# ASD2101.net
KiCad netlist of a schematic drawn in EAGLE
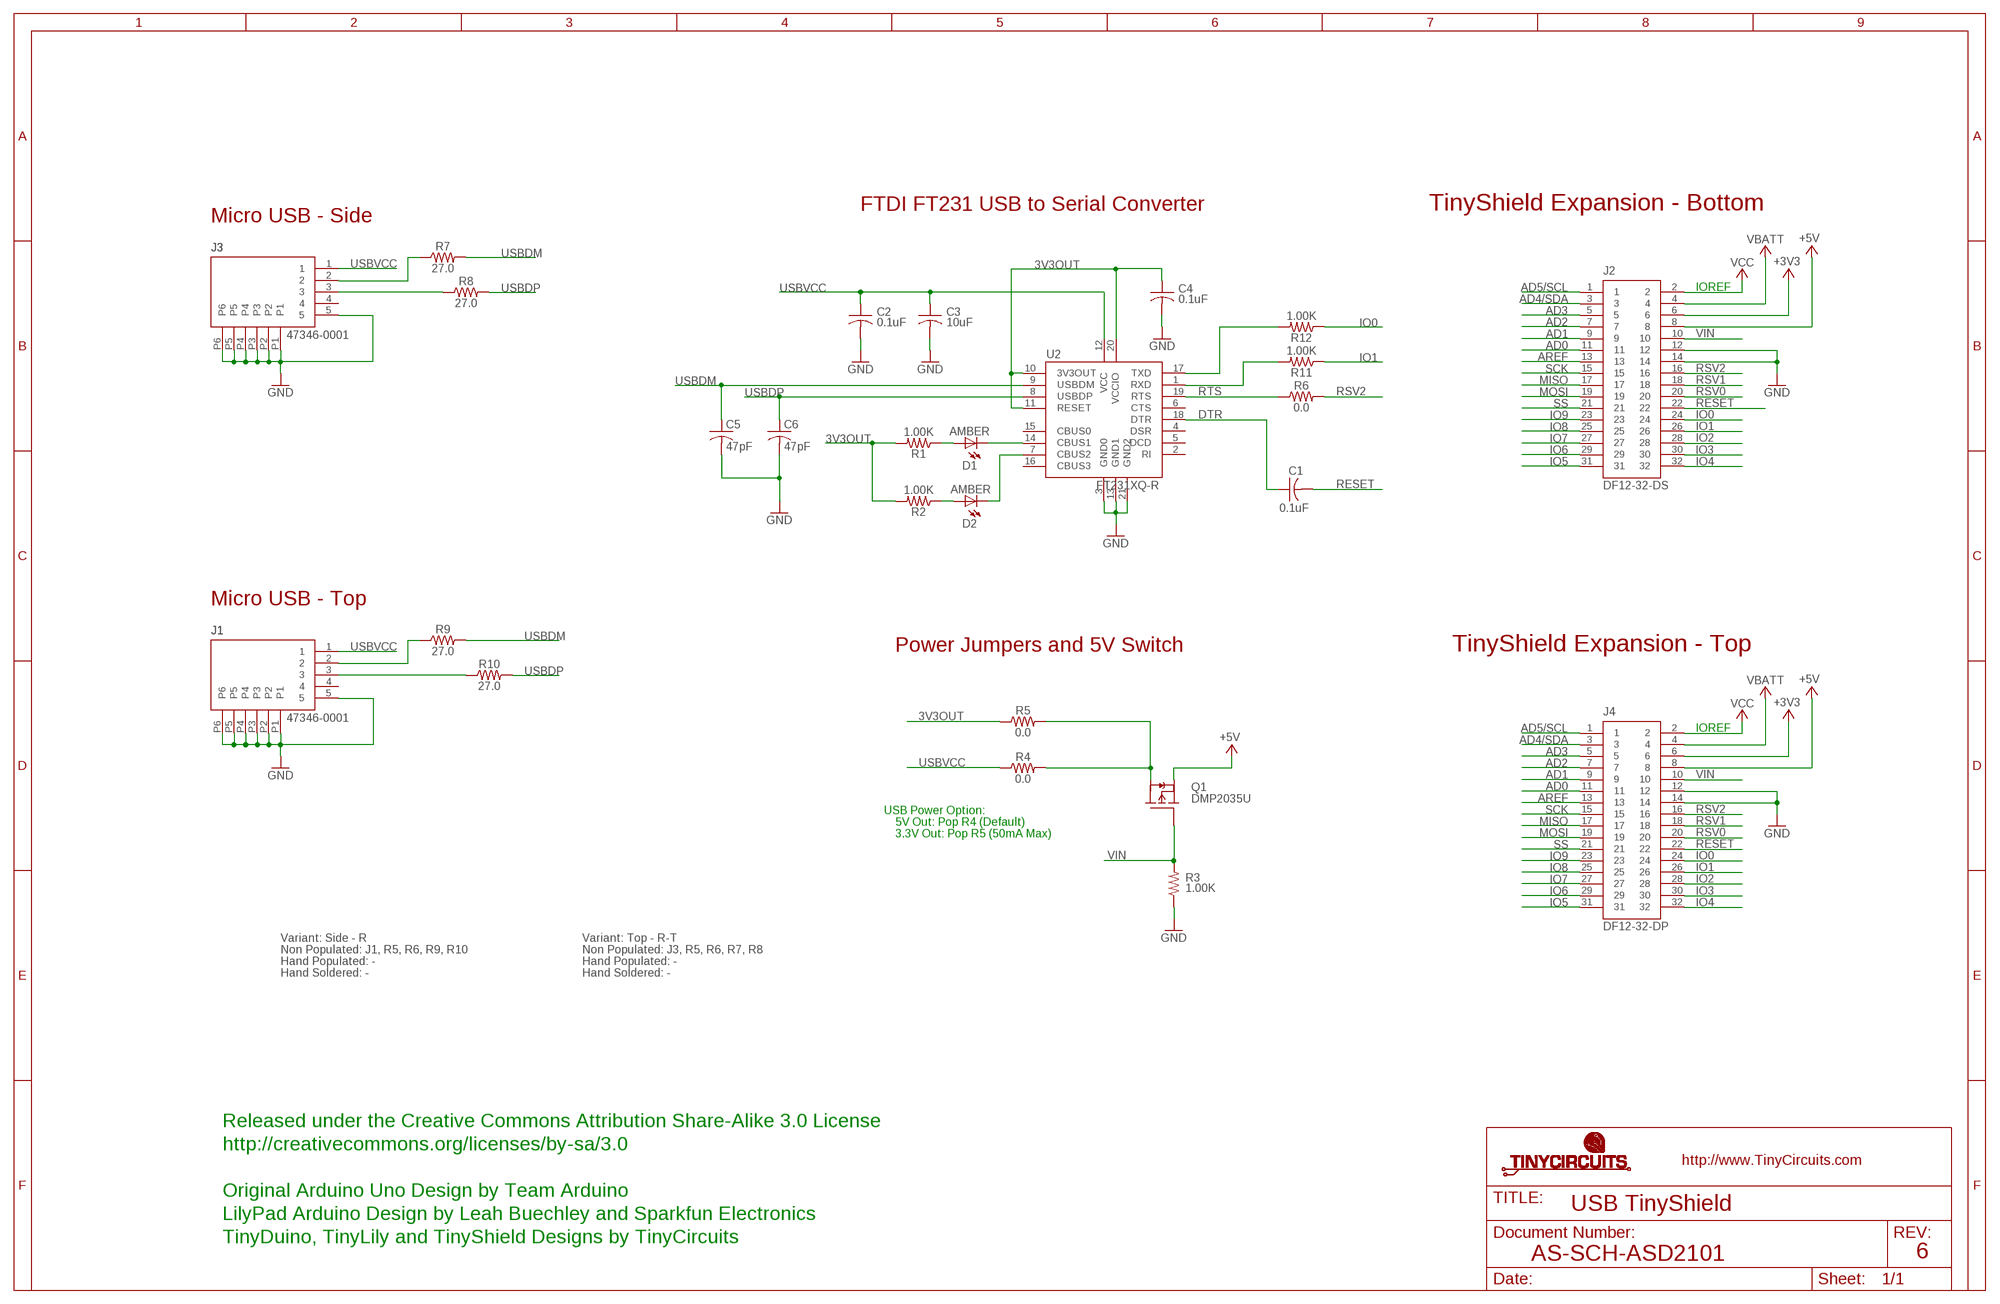
[diagram p0: schematic, sheet 1]

(export (version "E")
  (design (tool "Eeschema 10.0.6"))
  (components
    (comp (ref "C1")
      (value "0.1uF")
      (footprint "eagle-import:C0402")
      (fields (field (name "PARTNO") "AS-ITM-00008") (field (name "PARTNO_1") "AS-ITM-00008"))
      (libsource (lib "eagle-import") (part "AS-ITM-00008"))
    )
    (comp (ref "C2")
      (value "0.1uF")
      (footprint "eagle-import:C0402")
      (fields (field (name "PARTNO") "AS-ITM-00008"))
      (libsource (lib "eagle-import") (part "AS-ITM-00008"))
    )
    (comp (ref "C3")
      (value "10uF")
      (footprint "eagle-import:C0603")
      (fields (field (name "PARTNO") "AS-ITM-00002"))
      (libsource (lib "eagle-import") (part "AS-ITM-00002"))
    )
    (comp (ref "C4")
      (value "0.1uF")
      (footprint "eagle-import:C0402")
      (fields (field (name "PARTNO") "AS-ITM-00008") (field (name "PARTNO_1") "AS-ITM-00008"))
      (libsource (lib "eagle-import") (part "AS-ITM-00008"))
    )
    (comp (ref "C5")
      (value "47pF")
      (footprint "eagle-import:0402")
      (fields (field (name "PARTNO") "AS-ITM-00241") (field (name "PARTNO_1") "AS-ITM-00241"))
      (libsource (lib "eagle-import") (part "AS-ITM-00241"))
    )
    (comp (ref "C6")
      (value "47pF")
      (footprint "eagle-import:0402")
      (fields (field (name "PARTNO") "AS-ITM-00241") (field (name "PARTNO_1") "AS-ITM-00241"))
      (libsource (lib "eagle-import") (part "AS-ITM-00241"))
    )
    (comp (ref "D1")
      (value "AMBER")
      (footprint "eagle-import:LNJ_LED")
      (fields (field (name "PARTNO") "AS-ITM-00026"))
      (libsource (lib "eagle-import") (part "AS-ITM-00026"))
    )
    (comp (ref "D2")
      (value "AMBER")
      (footprint "eagle-import:LNJ_LED")
      (fields (field (name "PARTNO") "AS-ITM-00026"))
      (libsource (lib "eagle-import") (part "AS-ITM-00026"))
    )
    (comp (ref "J1")
      (value "47346-0001")
      (footprint "eagle-import:MICRO_USB")
      (fields (field (name "PARTNO") "AS-ITM-00021") (field (name "PARTNO_1") "AS-ITM-00021"))
      (libsource (lib "eagle-import") (part "AS-ITM-00021"))
    )
    (comp (ref "J2")
      (value "DF12-32-DS")
      (footprint "eagle-import:DF12-32-DS")
      (fields (field (name "PARTNO") "AS-ITM-00012") (field (name "PARTNO_1") "AS-ITM-00012"))
      (libsource (lib "eagle-import") (part "AS-ITM-00012"))
    )
    (comp (ref "J3")
      (value "47346-0001")
      (footprint "eagle-import:MICRO_USB")
      (fields (field (name "PARTNO") "AS-ITM-00021") (field (name "PARTNO_1") "AS-ITM-00021"))
      (libsource (lib "eagle-import") (part "AS-ITM-00021"))
    )
    (comp (ref "J4")
      (value "DF12-32-DP")
      (footprint "eagle-import:DF12-32-DP")
      (fields (field (name "PARTNO") "AS-ITM-00015") (field (name "PARTNO_1") "AS-ITM-00015"))
      (libsource (lib "eagle-import") (part "AS-ITM-00015"))
    )
    (comp (ref "Q1")
      (value "DMP2035U")
      (footprint "eagle-import:SOT23")
      (fields (field (name "PARTNO") "AS-ITM-00024"))
      (libsource (lib "eagle-import") (part "AS-ITM-00024"))
    )
    (comp (ref "R1")
      (value "1.00K")
      (footprint "eagle-import:0402")
      (fields (field (name "PARTNO") "AS-ITM-00003"))
      (libsource (lib "eagle-import") (part "AS-ITM-00003"))
    )
    (comp (ref "R2")
      (value "1.00K")
      (footprint "eagle-import:0402")
      (fields (field (name "PARTNO") "AS-ITM-00003"))
      (libsource (lib "eagle-import") (part "AS-ITM-00003"))
    )
    (comp (ref "R3")
      (value "1.00K")
      (footprint "eagle-import:0402")
      (fields (field (name "PARTNO") "AS-ITM-00003"))
      (libsource (lib "eagle-import") (part "AS-ITM-00003"))
    )
    (comp (ref "R4")
      (value "0.0")
      (footprint "eagle-import:0402")
      (fields (field (name "PARTNO") "AS-ITM-00076"))
      (libsource (lib "eagle-import") (part "AS-ITM-00076"))
    )
    (comp (ref "R5")
      (value "0.0")
      (footprint "eagle-import:0402")
      (fields (field (name "PARTNO") "AS-ITM-00076"))
      (libsource (lib "eagle-import") (part "AS-ITM-00076"))
    )
    (comp (ref "R6")
      (value "0.0")
      (footprint "eagle-import:0402_SHORT")
      (libsource (lib "eagle-import") (part "AS-ITM-000760402_SHORT"))
    )
    (comp (ref "R7")
      (value "27.0")
      (footprint "eagle-import:0402")
      (fields (field (name "PARTNO") "AS-ITM-00240"))
      (libsource (lib "eagle-import") (part "AS-ITM-00240"))
    )
    (comp (ref "R8")
      (value "27.0")
      (footprint "eagle-import:0402")
      (fields (field (name "PARTNO") "AS-ITM-00240"))
      (libsource (lib "eagle-import") (part "AS-ITM-00240"))
    )
    (comp (ref "R9")
      (value "27.0")
      (footprint "eagle-import:0402")
      (fields (field (name "PARTNO") "AS-ITM-00240"))
      (libsource (lib "eagle-import") (part "AS-ITM-00240"))
    )
    (comp (ref "R10")
      (value "27.0")
      (footprint "eagle-import:0402")
      (fields (field (name "PARTNO") "AS-ITM-00240"))
      (libsource (lib "eagle-import") (part "AS-ITM-00240"))
    )
    (comp (ref "R11")
      (value "1.00K")
      (footprint "eagle-import:0402")
      (fields (field (name "PARTNO") "AS-ITM-00003") (field (name "PARTNO_1") "AS-ITM-00003"))
      (libsource (lib "eagle-import") (part "AS-ITM-00003"))
    )
    (comp (ref "R12")
      (value "1.00K")
      (footprint "eagle-import:0402")
      (fields (field (name "PARTNO") "AS-ITM-00003") (field (name "PARTNO_1") "AS-ITM-00003"))
      (libsource (lib "eagle-import") (part "AS-ITM-00003"))
    )
    (comp (ref "U2")
      (value "FT231XQ-R")
      (footprint "eagle-import:QFN20")
      (fields (field (name "PARTNO") "AS-ITM-00223"))
      (libsource (lib "eagle-import") (part "AS-ITM-00223"))
    )
  )
  (nets
    (net (code "1") (name "+3V3") (class "Default")
      (node (ref "J2") (pin "6") (pinfunction "6_6") (pintype "bidirectional"))
      (node (ref "J4") (pin "6") (pinfunction "6_6") (pintype "bidirectional"))
    )
    (net (code "2") (name "+5V") (class "Default")
      (node (ref "J2") (pin "8") (pinfunction "8_8") (pintype "bidirectional"))
      (node (ref "J4") (pin "8") (pinfunction "8_8") (pintype "bidirectional"))
      (node (ref "Q1") (pin "E") (pinfunction "S_E") (pintype "passive"))
    )
    (net (code "3") (name "/3V3OUT") (class "Default")
      (node (ref "C4") (pin "1") (pinfunction "1_1") (pintype "passive"))
      (node (ref "R1") (pin "2") (pinfunction "2_2") (pintype "passive"))
      (node (ref "R2") (pin "2") (pinfunction "2_2") (pintype "passive"))
      (node (ref "R5") (pin "1") (pinfunction "1_1") (pintype "passive"))
      (node (ref "U2") (pin "10") (pinfunction "3V3OUT_10") (pintype "bidirectional"))
      (node (ref "U2") (pin "11") (pinfunction "RESET_11") (pintype "bidirectional"))
      (node (ref "U2") (pin "20") (pinfunction "VCCIO_20") (pintype "bidirectional"))
    )
    (net (code "4") (name "/AD0") (class "Default")
      (node (ref "J2") (pin "11") (pinfunction "11_11") (pintype "bidirectional"))
      (node (ref "J4") (pin "11") (pinfunction "11_11") (pintype "bidirectional"))
    )
    (net (code "5") (name "/AD1") (class "Default")
      (node (ref "J2") (pin "9") (pinfunction "9_9") (pintype "bidirectional"))
      (node (ref "J4") (pin "9") (pinfunction "9_9") (pintype "bidirectional"))
    )
    (net (code "6") (name "/AD2") (class "Default")
      (node (ref "J2") (pin "7") (pinfunction "7_7") (pintype "bidirectional"))
      (node (ref "J4") (pin "7") (pinfunction "7_7") (pintype "bidirectional"))
    )
    (net (code "7") (name "/AD3") (class "Default")
      (node (ref "J2") (pin "5") (pinfunction "5_5") (pintype "bidirectional"))
      (node (ref "J4") (pin "5") (pinfunction "5_5") (pintype "bidirectional"))
    )
    (net (code "8") (name "/AD4{slash}SDA") (class "Default")
      (node (ref "J2") (pin "3") (pinfunction "3_3") (pintype "bidirectional"))
      (node (ref "J4") (pin "3") (pinfunction "3_3") (pintype "bidirectional"))
    )
    (net (code "9") (name "/AD5{slash}SCL") (class "Default")
      (node (ref "J2") (pin "1") (pinfunction "1_1") (pintype "bidirectional"))
      (node (ref "J4") (pin "1") (pinfunction "1_1") (pintype "bidirectional"))
    )
    (net (code "10") (name "/AREF") (class "Default")
      (node (ref "J2") (pin "13") (pinfunction "13_13") (pintype "bidirectional"))
      (node (ref "J4") (pin "13") (pinfunction "13_13") (pintype "bidirectional"))
    )
    (net (code "11") (name "/DTR") (class "Default")
      (node (ref "C1") (pin "1") (pinfunction "1_1") (pintype "passive"))
      (node (ref "U2") (pin "18") (pinfunction "DTR_18") (pintype "bidirectional"))
    )
    (net (code "12") (name "/IO0") (class "Default")
      (node (ref "J2") (pin "24") (pinfunction "24_24") (pintype "bidirectional"))
      (node (ref "J4") (pin "24") (pinfunction "24_24") (pintype "bidirectional"))
      (node (ref "R12") (pin "1") (pinfunction "1_1") (pintype "passive"))
    )
    (net (code "13") (name "/IO1") (class "Default")
      (node (ref "J2") (pin "26") (pinfunction "26_26") (pintype "bidirectional"))
      (node (ref "J4") (pin "26") (pinfunction "26_26") (pintype "bidirectional"))
      (node (ref "R11") (pin "1") (pinfunction "1_1") (pintype "passive"))
    )
    (net (code "14") (name "/IO2") (class "Default")
      (node (ref "J2") (pin "28") (pinfunction "28_28") (pintype "bidirectional"))
      (node (ref "J4") (pin "28") (pinfunction "28_28") (pintype "bidirectional"))
    )
    (net (code "15") (name "/IO3") (class "Default")
      (node (ref "J2") (pin "30") (pinfunction "30_30") (pintype "bidirectional"))
      (node (ref "J4") (pin "30") (pinfunction "30_30") (pintype "bidirectional"))
    )
    (net (code "16") (name "/IO4") (class "Default")
      (node (ref "J2") (pin "32") (pinfunction "32_32") (pintype "bidirectional"))
      (node (ref "J4") (pin "32") (pinfunction "32_32") (pintype "bidirectional"))
    )
    (net (code "17") (name "/IO5") (class "Default")
      (node (ref "J2") (pin "31") (pinfunction "31_31") (pintype "bidirectional"))
      (node (ref "J4") (pin "31") (pinfunction "31_31") (pintype "bidirectional"))
    )
    (net (code "18") (name "/IO6") (class "Default")
      (node (ref "J2") (pin "29") (pinfunction "29_29") (pintype "bidirectional"))
      (node (ref "J4") (pin "29") (pinfunction "29_29") (pintype "bidirectional"))
    )
    (net (code "19") (name "/IO7") (class "Default")
      (node (ref "J2") (pin "27") (pinfunction "27_27") (pintype "bidirectional"))
      (node (ref "J4") (pin "27") (pinfunction "27_27") (pintype "bidirectional"))
    )
    (net (code "20") (name "/IO8") (class "Default")
      (node (ref "J2") (pin "25") (pinfunction "25_25") (pintype "bidirectional"))
      (node (ref "J4") (pin "25") (pinfunction "25_25") (pintype "bidirectional"))
    )
    (net (code "21") (name "/IO9") (class "Default")
      (node (ref "J2") (pin "23") (pinfunction "23_23") (pintype "bidirectional"))
      (node (ref "J4") (pin "23") (pinfunction "23_23") (pintype "bidirectional"))
    )
    (net (code "22") (name "/MISO") (class "Default")
      (node (ref "J2") (pin "17") (pinfunction "17_17") (pintype "bidirectional"))
      (node (ref "J4") (pin "17") (pinfunction "17_17") (pintype "bidirectional"))
    )
    (net (code "23") (name "/MOSI") (class "Default")
      (node (ref "J2") (pin "19") (pinfunction "19_19") (pintype "bidirectional"))
      (node (ref "J4") (pin "19") (pinfunction "19_19") (pintype "bidirectional"))
    )
    (net (code "24") (name "/RESET") (class "Default")
      (node (ref "C1") (pin "2") (pinfunction "2_2") (pintype "passive"))
      (node (ref "J2") (pin "22") (pinfunction "22_22") (pintype "bidirectional"))
      (node (ref "J4") (pin "22") (pinfunction "22_22") (pintype "bidirectional"))
    )
    (net (code "25") (name "/RSV0") (class "Default")
      (node (ref "J2") (pin "20") (pinfunction "20_20") (pintype "bidirectional"))
      (node (ref "J4") (pin "20") (pinfunction "20_20") (pintype "bidirectional"))
    )
    (net (code "26") (name "/RSV1") (class "Default")
      (node (ref "J2") (pin "18") (pinfunction "18_18") (pintype "bidirectional"))
      (node (ref "J4") (pin "18") (pinfunction "18_18") (pintype "bidirectional"))
    )
    (net (code "27") (name "/RSV2") (class "Default")
      (node (ref "J2") (pin "16") (pinfunction "16_16") (pintype "bidirectional"))
      (node (ref "J4") (pin "16") (pinfunction "16_16") (pintype "bidirectional"))
      (node (ref "R6") (pin "2") (pinfunction "2_2") (pintype "passive"))
    )
    (net (code "28") (name "/RTS") (class "Default")
      (node (ref "R6") (pin "1") (pinfunction "1_1") (pintype "passive"))
      (node (ref "U2") (pin "19") (pinfunction "RTS_19") (pintype "bidirectional"))
    )
    (net (code "29") (name "/SCK") (class "Default")
      (node (ref "J2") (pin "15") (pinfunction "15_15") (pintype "bidirectional"))
      (node (ref "J4") (pin "15") (pinfunction "15_15") (pintype "bidirectional"))
    )
    (net (code "30") (name "/SS") (class "Default")
      (node (ref "J2") (pin "21") (pinfunction "21_21") (pintype "bidirectional"))
      (node (ref "J4") (pin "21") (pinfunction "21_21") (pintype "bidirectional"))
    )
    (net (code "31") (name "/USBDM") (class "Default")
      (node (ref "C5") (pin "1") (pinfunction "1_1") (pintype "passive"))
      (node (ref "R7") (pin "2") (pinfunction "2_2") (pintype "passive"))
      (node (ref "R9") (pin "2") (pinfunction "2_2") (pintype "passive"))
      (node (ref "U2") (pin "9") (pinfunction "USBDM_9") (pintype "bidirectional"))
    )
    (net (code "32") (name "/USBDP") (class "Default")
      (node (ref "C6") (pin "1") (pinfunction "1_1") (pintype "passive"))
      (node (ref "R10") (pin "2") (pinfunction "2_2") (pintype "passive"))
      (node (ref "R8") (pin "2") (pinfunction "2_2") (pintype "passive"))
      (node (ref "U2") (pin "8") (pinfunction "USBDP_8") (pintype "bidirectional"))
    )
    (net (code "33") (name "/USBVCC") (class "Default")
      (node (ref "C2") (pin "1") (pinfunction "1_1") (pintype "passive"))
      (node (ref "C3") (pin "1") (pinfunction "1_1") (pintype "passive"))
      (node (ref "J1") (pin "1") (pinfunction "1_1") (pintype "bidirectional"))
      (node (ref "J3") (pin "1") (pinfunction "1_1") (pintype "bidirectional"))
      (node (ref "R4") (pin "1") (pinfunction "1_1") (pintype "passive"))
      (node (ref "U2") (pin "12") (pinfunction "VCC_12") (pintype "bidirectional"))
    )
    (net (code "34") (name "/VIN") (class "Default")
      (node (ref "J2") (pin "10") (pinfunction "10_10") (pintype "bidirectional"))
      (node (ref "J4") (pin "10") (pinfunction "10_10") (pintype "bidirectional"))
      (node (ref "Q1") (pin "B") (pinfunction "G_B") (pintype "passive"))
      (node (ref "R3") (pin "2") (pinfunction "2_2") (pintype "passive"))
    )
    (net (code "35") (name "GND") (class "Default")
      (node (ref "C2") (pin "2") (pinfunction "2_2") (pintype "passive"))
      (node (ref "C3") (pin "2") (pinfunction "2_2") (pintype "passive"))
      (node (ref "C4") (pin "2") (pinfunction "2_2") (pintype "passive"))
      (node (ref "C5") (pin "2") (pinfunction "2_2") (pintype "passive"))
      (node (ref "C6") (pin "2") (pinfunction "2_2") (pintype "passive"))
      (node (ref "J1") (pin "5") (pinfunction "5_5") (pintype "bidirectional"))
      (node (ref "J1") (pin "P1") (pinfunction "P1_P1") (pintype "bidirectional"))
      (node (ref "J1") (pin "P2") (pinfunction "P2_P2") (pintype "bidirectional"))
      (node (ref "J1") (pin "P3") (pinfunction "P3_P3") (pintype "bidirectional"))
      (node (ref "J1") (pin "P4") (pinfunction "P4_P4") (pintype "bidirectional"))
      (node (ref "J1") (pin "P5") (pinfunction "P5_P5") (pintype "bidirectional"))
      (node (ref "J1") (pin "P6") (pinfunction "P6_P6") (pintype "bidirectional"))
      (node (ref "J2") (pin "12") (pinfunction "12_12") (pintype "bidirectional"))
      (node (ref "J2") (pin "14") (pinfunction "14_14") (pintype "bidirectional"))
      (node (ref "J3") (pin "5") (pinfunction "5_5") (pintype "bidirectional"))
      (node (ref "J3") (pin "P1") (pinfunction "P1_P1") (pintype "bidirectional"))
      (node (ref "J3") (pin "P2") (pinfunction "P2_P2") (pintype "bidirectional"))
      (node (ref "J3") (pin "P3") (pinfunction "P3_P3") (pintype "bidirectional"))
      (node (ref "J3") (pin "P4") (pinfunction "P4_P4") (pintype "bidirectional"))
      (node (ref "J3") (pin "P5") (pinfunction "P5_P5") (pintype "bidirectional"))
      (node (ref "J3") (pin "P6") (pinfunction "P6_P6") (pintype "bidirectional"))
      (node (ref "J4") (pin "12") (pinfunction "12_12") (pintype "bidirectional"))
      (node (ref "J4") (pin "14") (pinfunction "14_14") (pintype "bidirectional"))
      (node (ref "R3") (pin "1") (pinfunction "1_1") (pintype "passive"))
      (node (ref "U2") (pin "13") (pinfunction "GND1_13") (pintype "bidirectional"))
      (node (ref "U2") (pin "21") (pinfunction "GND2_21") (pintype "bidirectional"))
      (node (ref "U2") (pin "3") (pinfunction "GND0_3") (pintype "bidirectional"))
    )
    (net (code "36") (name "Net-(D1-PadA)") (class "Default")
      (node (ref "D1") (pin "A") (pinfunction "A_A") (pintype "passive"))
      (node (ref "R1") (pin "1") (pinfunction "1_1") (pintype "passive"))
    )
    (net (code "37") (name "Net-(D2-PadA)") (class "Default")
      (node (ref "D2") (pin "A") (pinfunction "A_A") (pintype "passive"))
      (node (ref "R2") (pin "1") (pinfunction "1_1") (pintype "passive"))
    )
    (net (code "38") (name "Net-(J1-Pad2)") (class "Default")
      (node (ref "J1") (pin "2") (pinfunction "2_2") (pintype "bidirectional"))
      (node (ref "R9") (pin "1") (pinfunction "1_1") (pintype "passive"))
    )
    (net (code "39") (name "Net-(J1-Pad3)") (class "Default")
      (node (ref "J1") (pin "3") (pinfunction "3_3") (pintype "bidirectional"))
      (node (ref "R10") (pin "1") (pinfunction "1_1") (pintype "passive"))
    )
    (net (code "40") (name "Net-(J3-Pad2)") (class "Default")
      (node (ref "J3") (pin "2") (pinfunction "2_2") (pintype "bidirectional"))
      (node (ref "R7") (pin "1") (pinfunction "1_1") (pintype "passive"))
    )
    (net (code "41") (name "Net-(J3-Pad3)") (class "Default")
      (node (ref "J3") (pin "3") (pinfunction "3_3") (pintype "bidirectional"))
      (node (ref "R8") (pin "1") (pinfunction "1_1") (pintype "passive"))
    )
    (net (code "42") (name "Net-(Q1-D)") (class "Default")
      (node (ref "Q1") (pin "C") (pinfunction "D_C") (pintype "passive"))
      (node (ref "R4") (pin "2") (pinfunction "2_2") (pintype "passive"))
      (node (ref "R5") (pin "2") (pinfunction "2_2") (pintype "passive"))
    )
    (net (code "43") (name "Net-(U2-CBUS1)") (class "Default")
      (node (ref "D1") (pin "C") (pinfunction "C_C") (pintype "passive"))
      (node (ref "U2") (pin "14") (pinfunction "CBUS1_14") (pintype "bidirectional"))
    )
    (net (code "44") (name "Net-(U2-CBUS2)") (class "Default")
      (node (ref "D2") (pin "C") (pinfunction "C_C") (pintype "passive"))
      (node (ref "U2") (pin "7") (pinfunction "CBUS2_7") (pintype "bidirectional"))
    )
    (net (code "45") (name "Net-(U2-RXD)") (class "Default")
      (node (ref "R11") (pin "2") (pinfunction "2_2") (pintype "passive"))
      (node (ref "U2") (pin "1") (pinfunction "RXD_1") (pintype "bidirectional"))
    )
    (net (code "46") (name "Net-(U2-TXD)") (class "Default")
      (node (ref "R12") (pin "2") (pinfunction "2_2") (pintype "passive"))
      (node (ref "U2") (pin "17") (pinfunction "TXD_17") (pintype "bidirectional"))
    )
    (net (code "47") (name "VBATT") (class "Default")
      (node (ref "J2") (pin "4") (pinfunction "4_4") (pintype "bidirectional"))
      (node (ref "J4") (pin "4") (pinfunction "4_4") (pintype "bidirectional"))
    )
    (net (code "48") (name "VCC") (class "Default")
      (node (ref "J2") (pin "2") (pinfunction "2_2") (pintype "bidirectional"))
      (node (ref "J4") (pin "2") (pinfunction "2_2") (pintype "bidirectional"))
    )
    (net (code "49") (name "unconnected-(J1-Pad4)") (class "Default")
      (node (ref "J1") (pin "4") (pinfunction "4_4") (pintype "bidirectional"))
    )
    (net (code "50") (name "unconnected-(J3-Pad4)") (class "Default")
      (node (ref "J3") (pin "4") (pinfunction "4_4") (pintype "bidirectional"))
    )
    (net (code "51") (name "unconnected-(U2-CBUS0-Pad15)") (class "Default")
      (node (ref "U2") (pin "15") (pinfunction "CBUS0_15") (pintype "bidirectional"))
    )
    (net (code "52") (name "unconnected-(U2-CBUS3-Pad16)") (class "Default")
      (node (ref "U2") (pin "16") (pinfunction "CBUS3_16") (pintype "bidirectional"))
    )
    (net (code "53") (name "unconnected-(U2-CTS-Pad6)") (class "Default")
      (node (ref "U2") (pin "6") (pinfunction "CTS_6") (pintype "bidirectional"))
    )
    (net (code "54") (name "unconnected-(U2-DCD-Pad5)") (class "Default")
      (node (ref "U2") (pin "5") (pinfunction "DCD_5") (pintype "bidirectional"))
    )
    (net (code "55") (name "unconnected-(U2-DSR-Pad4)") (class "Default")
      (node (ref "U2") (pin "4") (pinfunction "DSR_4") (pintype "bidirectional"))
    )
    (net (code "56") (name "unconnected-(U2-RI-Pad2)") (class "Default")
      (node (ref "U2") (pin "2") (pinfunction "RI_2") (pintype "bidirectional"))
    )
  )
)
